# fiber.net
KiCad netlist of a schematic drawn in Altium Designer
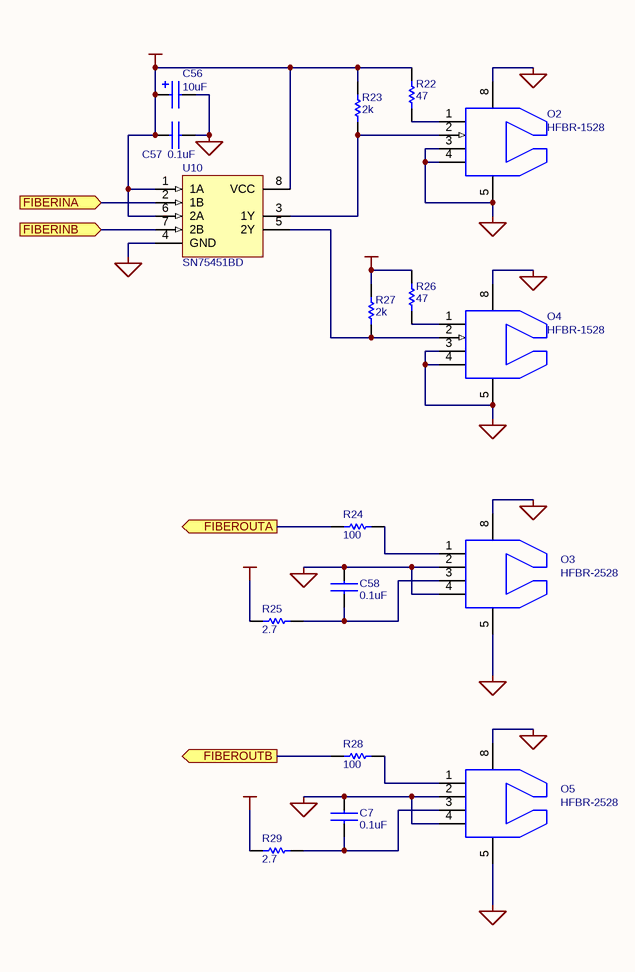
[diagram p0: fiber.SCHDOC]

(export (version "E")
  (design (tool "Eeschema 10.0.6"))
  (components
    (comp (ref "C7")
      (value "0.1uF")
      (footprint "0603")
      (description "Standard Capacitor")
      (fields (field (name "Comment") "CAPACITOR"))
      (libsource (lib "parts") (part "CAPACITOR"))
    )
    (comp (ref "C56")
      (value "10uF")
      (footprint "3216")
      (description "Standard Capacitor")
      (fields (field (name "Comment") "Bypass Cap"))
      (libsource (lib "parts") (part "POLCAP"))
    )
    (comp (ref "C57")
      (value "0.1uF")
      (footprint "0603")
      (description "Standard Capacitor")
      (fields (field (name "Comment") "CAPACITOR"))
      (libsource (lib "parts") (part "CAPACITOR"))
    )
    (comp (ref "C58")
      (value "0.1uF")
      (footprint "0603")
      (description "Standard Capacitor")
      (fields (field (name "Comment") "CAPACITOR"))
      (libsource (lib "parts") (part "CAPACITOR"))
    )
    (comp (ref "O2")
      (value "HFBR-1528")
      (footprint "HPVL")
      (description "Low-cost fiber transmitter")
      (libsource (lib "parts") (part "HFBR-1528"))
    )
    (comp (ref "O3")
      (value "HFBR-2528")
      (footprint "HPVL")
      (description "Low-cost fiber receiver")
      (libsource (lib "parts") (part "HFBR-2528"))
    )
    (comp (ref "O4")
      (value "HFBR-1528")
      (footprint "HPVL")
      (description "Low-cost fiber transmitter")
      (libsource (lib "parts") (part "HFBR-1528"))
    )
    (comp (ref "O5")
      (value "HFBR-2528")
      (footprint "HPVL")
      (description "Low-cost fiber receiver")
      (libsource (lib "parts") (part "HFBR-2528"))
    )
    (comp (ref "R22")
      (value "47")
      (footprint "0603")
      (description "Standard Passive Resistor")
      (fields (field (name "Comment") "RESISTOR"))
      (libsource (lib "parts") (part "RESISTOR"))
    )
    (comp (ref "R23")
      (value "2k")
      (footprint "0603")
      (description "Standard Passive Resistor")
      (fields (field (name "Comment") "RESISTOR"))
      (libsource (lib "parts") (part "RESISTOR"))
    )
    (comp (ref "R24")
      (value "100")
      (footprint "0603")
      (description "Standard Passive Resistor")
      (fields (field (name "Comment") "RESISTOR"))
      (libsource (lib "parts") (part "RESISTOR"))
    )
    (comp (ref "R25")
      (value "2.7")
      (footprint "0603")
      (description "Standard Passive Resistor")
      (fields (field (name "Comment") "RESISTOR"))
      (libsource (lib "parts") (part "RESISTOR"))
    )
    (comp (ref "R26")
      (value "47")
      (footprint "0603")
      (description "Standard Passive Resistor")
      (fields (field (name "Comment") "RESISTOR"))
      (libsource (lib "parts") (part "RESISTOR"))
    )
    (comp (ref "R27")
      (value "2k")
      (footprint "0603")
      (description "Standard Passive Resistor")
      (fields (field (name "Comment") "RESISTOR"))
      (libsource (lib "parts") (part "RESISTOR"))
    )
    (comp (ref "R28")
      (value "100")
      (footprint "0603")
      (description "Standard Passive Resistor")
      (fields (field (name "Comment") "RESISTOR"))
      (libsource (lib "parts") (part "RESISTOR"))
    )
    (comp (ref "R29")
      (value "2.7")
      (footprint "0603")
      (description "Standard Passive Resistor")
      (fields (field (name "Comment") "RESISTOR"))
      (libsource (lib "parts") (part "RESISTOR"))
    )
    (comp (ref "U10")
      (value "SN75451BD")
      (footprint "SO-G8/E2.5")
      (description "Dual Peripheral Driver")
      (fields (field (name "MANUFACTURER") "Texas Instruments") (field (name "PUBLISHER") "Altium Limited"))
      (libsource (lib "TI Interface Peripheral Driver") (part "SN75451BD"))
    )
  )
  (nets
    (net (code "1") (name "+5VCC") (class "Default")
      (node (ref "C56") (pin "1") (pintype "passive"))
      (node (ref "C57") (pin "1") (pintype "passive"))
      (node (ref "R22") (pin "2") (pintype "passive"))
      (node (ref "R23") (pin "2") (pintype "passive"))
      (node (ref "R25") (pin "1") (pintype "passive"))
      (node (ref "R26") (pin "2") (pintype "passive"))
      (node (ref "R27") (pin "2") (pintype "passive"))
      (node (ref "R29") (pin "1") (pintype "passive"))
      (node (ref "U10") (pin "1") (pinfunction "1A_1") (pintype "input"))
      (node (ref "U10") (pin "6") (pinfunction "2A_6") (pintype "input"))
      (node (ref "U10") (pin "8") (pinfunction "VCC_8") (pintype "power_in"))
    )
    (net (code "2") (name "/FIBERINA") (class "Default")
      (node (ref "U10") (pin "2") (pinfunction "1B_2") (pintype "input"))
    )
    (net (code "3") (name "/FIBERINB") (class "Default")
      (node (ref "U10") (pin "7") (pinfunction "2B_7") (pintype "input"))
    )
    (net (code "4") (name "/FIBEROUTA") (class "Default") (node (ref "R24") (pin "1") (pintype "passive")))
    (net (code "5") (name "/FIBEROUTB") (class "Default") (node (ref "R28") (pin "1") (pintype "passive")))
    (net (code "6") (name "GND") (class "Default")
      (node (ref "C56") (pin "2") (pintype "passive"))
      (node (ref "C57") (pin "2") (pintype "passive"))
      (node (ref "C58") (pin "2") (pintype "passive"))
      (node (ref "C7") (pin "2") (pintype "passive"))
      (node (ref "O2") (pin "3") (pintype "power_in"))
      (node (ref "O2") (pin "4") (pintype "power_in"))
      (node (ref "O2") (pin "5") (pintype "power_in"))
      (node (ref "O2") (pin "8") (pintype "power_in"))
      (node (ref "O3") (pin "2") (pintype "power_in"))
      (node (ref "O3") (pin "4") (pintype "power_in"))
      (node (ref "O3") (pin "5") (pintype "power_in"))
      (node (ref "O3") (pin "8") (pintype "power_in"))
      (node (ref "O4") (pin "3") (pintype "power_in"))
      (node (ref "O4") (pin "4") (pintype "power_in"))
      (node (ref "O4") (pin "5") (pintype "power_in"))
      (node (ref "O4") (pin "8") (pintype "power_in"))
      (node (ref "O5") (pin "2") (pintype "power_in"))
      (node (ref "O5") (pin "4") (pintype "power_in"))
      (node (ref "O5") (pin "5") (pintype "power_in"))
      (node (ref "O5") (pin "8") (pintype "power_in"))
      (node (ref "U10") (pin "4") (pinfunction "GND_4") (pintype "power_in"))
    )
    (net (code "7") (name "Net-(C7-Pad1)") (class "Default")
      (node (ref "C7") (pin "1") (pintype "passive"))
      (node (ref "O5") (pin "3") (pintype "power_in"))
      (node (ref "R29") (pin "2") (pintype "passive"))
    )
    (net (code "8") (name "Net-(C58-Pad1)") (class "Default")
      (node (ref "C58") (pin "1") (pintype "passive"))
      (node (ref "O3") (pin "3") (pintype "power_in"))
      (node (ref "R25") (pin "2") (pintype "passive"))
    )
    (net (code "9") (name "Net-(O2-Pad1)") (class "Default")
      (node (ref "O2") (pin "1") (pintype "power_in"))
      (node (ref "R22") (pin "1") (pintype "passive"))
    )
    (net (code "10") (name "Net-(O3-Pad1)") (class "Default")
      (node (ref "O3") (pin "1") (pintype "power_in"))
      (node (ref "R24") (pin "2") (pintype "passive"))
    )
    (net (code "11") (name "Net-(O4-Pad1)") (class "Default")
      (node (ref "O4") (pin "1") (pintype "power_in"))
      (node (ref "R26") (pin "1") (pintype "passive"))
    )
    (net (code "12") (name "Net-(O5-Pad1)") (class "Default")
      (node (ref "O5") (pin "1") (pintype "power_in"))
      (node (ref "R28") (pin "2") (pintype "passive"))
    )
    (net (code "13") (name "Net-(U10-1Y)") (class "Default")
      (node (ref "O2") (pin "2") (pintype "input"))
      (node (ref "R23") (pin "1") (pintype "passive"))
      (node (ref "U10") (pin "3") (pinfunction "1Y_3") (pintype "open_collector"))
    )
    (net (code "14") (name "Net-(U10-2Y)") (class "Default")
      (node (ref "O4") (pin "2") (pintype "input"))
      (node (ref "R27") (pin "1") (pintype "passive"))
      (node (ref "U10") (pin "5") (pinfunction "2Y_5") (pintype "open_collector"))
    )
  )
)
